# 09-modem3.net
KiCad netlist of a schematic drawn in Altium Designer
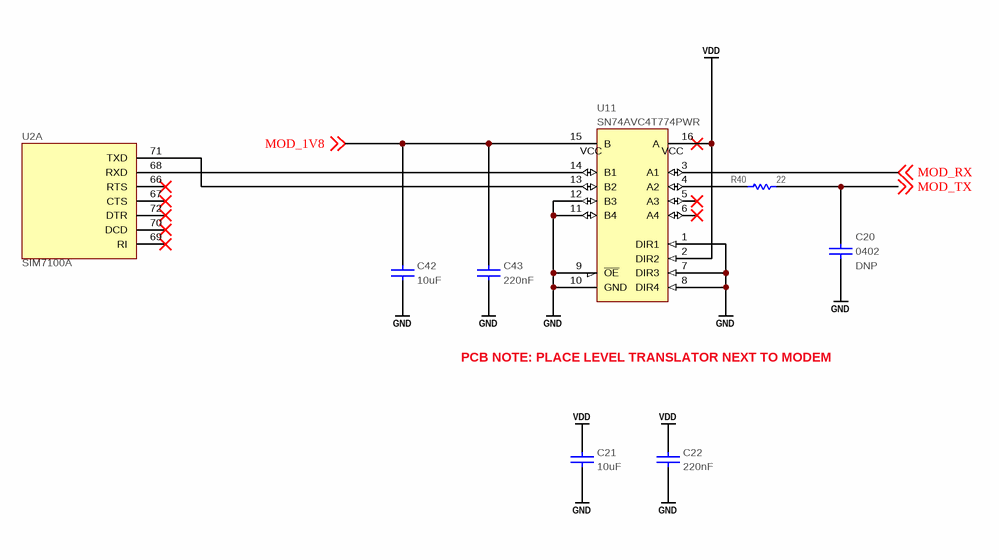
[diagram p0: 09-modem3.SchDoc]

(export (version "E")
  (design (tool "Eeschema 10.0.6"))
  (components
    (comp (ref "C20")
      (value "VJ0402A101KXA")
      (footprint "CAPC100X50X55L25N")
      (description "Ceramic Capacitor 100pF ±10% 50V C0G 0402")
      (fields
        (field (name "MANUFACTURER") "Vishay")
        (field (name "TOLERANCE") "±10%")
        (field (name "PACKAGE") "0402")
        (field (name "DO NOT PLACE") "DNP")
      )
      (libsource (lib "capacitors") (part "CAP"))
    )
    (comp (ref "C21")
      (value "10uF")
      (footprint "CAPC200X125X145L45N")
      (description "Ceramic Capacitor 10uF ±10% 16V X7R 0805")
      (fields (field (name "MANUFACTURER") "Samsung") (field (name "TOLERANCE") "±10%"))
      (libsource (lib "capacitors") (part "CAP"))
    )
    (comp (ref "C22")
      (value "220nF")
      (footprint "CAPC100X50X55L25N")
      (description "Ceramic Capacitor 220nF ±10% 25V X7R 0402")
      (fields (field (name "MANUFACTURER") "TDK") (field (name "TOLERANCE") "±10%"))
      (libsource (lib "capacitors") (part "CAP"))
    )
    (comp (ref "C42")
      (value "10uF")
      (footprint "CAPC200X125X145L45N")
      (description "Ceramic Capacitor 10uF ±10% 16V X7R 0805")
      (fields (field (name "MANUFACTURER") "Samsung") (field (name "TOLERANCE") "±10%"))
      (libsource (lib "capacitors") (part "CAP"))
    )
    (comp (ref "C43")
      (value "220nF")
      (footprint "CAPC100X50X55L25N")
      (description "Ceramic Capacitor 220nF ±10% 25V X7R 0402")
      (fields (field (name "MANUFACTURER") "TDK") (field (name "TOLERANCE") "±10%"))
      (libsource (lib "capacitors") (part "CAP"))
    )
    (comp (ref "R40")
      (value "22")
      (footprint "RESC2012X70N")
      (description "Thick Film Resistor 22 ±1% 0805")
      (fields (field (name "MANUFACTURER") "Panasonic") (field (name "TOLERANCE") "±1%"))
      (libsource (lib "Graviton") (part "RES 0402"))
    )
    (comp (ref "U2")
      (value "SIM7100A")
      (footprint "SIM7100A")
      (description "Cellular Module")
      (fields (field (name "MANUFACTURER") "SIMCOM"))
      (libsource (lib "simcom") (part "Component_1"))
    )
    (comp (ref "U11")
      (value "SN74AVC4T774PWR")
      (footprint "TSSOP16")
      (description "4-Bit Dual-Supply Bus Transceiver")
      (fields (field (name "MANUFACTURER") "Texas Instruments"))
      (libsource (lib "ti") (part "SN74AVC4T774PWR"))
    )
  )
  (nets
    (net (code "1") (name "GND") (class "Default")
      (node (ref "C20") (pin "2") (pinfunction "2_2") (pintype "passive"))
      (node (ref "C21") (pin "2") (pinfunction "2_2") (pintype "passive"))
      (node (ref "C22") (pin "2") (pinfunction "2_2") (pintype "passive"))
      (node (ref "C42") (pin "2") (pinfunction "2_2") (pintype "passive"))
      (node (ref "C43") (pin "2") (pinfunction "2_2") (pintype "passive"))
      (node (ref "U11") (pin "1") (pinfunction "DIR1_1") (pintype "input"))
      (node (ref "U11") (pin "10") (pinfunction "GND_10") (pintype "power_in"))
      (node (ref "U11") (pin "11") (pinfunction "B4_11") (pintype "bidirectional"))
      (node (ref "U11") (pin "12") (pinfunction "B3_12") (pintype "bidirectional"))
      (node (ref "U11") (pin "7") (pinfunction "DIR3_7") (pintype "input"))
      (node (ref "U11") (pin "8") (pinfunction "DIR4_8") (pintype "input"))
      (node (ref "U11") (pin "9") (pinfunction "OE_9") (pintype "passive"))
    )
    (net (code "2") (name "MOD_1V8") (class "Default")
      (node (ref "C42") (pin "1") (pinfunction "1_1") (pintype "passive"))
      (node (ref "C43") (pin "1") (pinfunction "1_1") (pintype "passive"))
      (node (ref "U11") (pin "15") (pinfunction "B_15") (pintype "power_in"))
    )
    (net (code "3") (name "MOD_RX") (class "Default")
      (node (ref "U11") (pin "3") (pinfunction "A1_3") (pintype "bidirectional"))
    )
    (net (code "4") (name "MOD_TX") (class "Default")
      (node (ref "C20") (pin "1") (pinfunction "1_1") (pintype "passive"))
      (node (ref "R40") (pin "1") (pinfunction "1_1") (pintype "passive"))
    )
    (net (code "5") (name "Net-(U11-A2)") (class "Default")
      (node (ref "R40") (pin "2") (pinfunction "2_2") (pintype "passive"))
      (node (ref "U11") (pin "4") (pinfunction "A2_4") (pintype "bidirectional"))
    )
    (net (code "6") (name "Net-(U11-B1)") (class "Default")
      (node (ref "U11") (pin "14") (pinfunction "B1_14") (pintype "bidirectional"))
      (node (ref "U2") (pin "68") (pinfunction "RXD_68") (pintype "passive"))
    )
    (net (code "7") (name "Net-(U11-B2)") (class "Default")
      (node (ref "U11") (pin "13") (pinfunction "B2_13") (pintype "bidirectional"))
      (node (ref "U2") (pin "71") (pinfunction "TXD_71") (pintype "passive"))
    )
    (net (code "8") (name "VDD") (class "Default")
      (node (ref "C21") (pin "1") (pinfunction "1_1") (pintype "passive"))
      (node (ref "C22") (pin "1") (pinfunction "1_1") (pintype "passive"))
      (node (ref "U11") (pin "16") (pinfunction "A_16") (pintype "power_in"))
      (node (ref "U11") (pin "2") (pinfunction "DIR2_2") (pintype "input"))
    )
    (net (code "9") (name "unconnected-(U2A-CTS-Pad67)") (class "Default")
      (node (ref "U2") (pin "67") (pinfunction "CTS_67") (pintype "passive+no_connect"))
    )
    (net (code "10") (name "unconnected-(U2A-DCD-Pad70)") (class "Default")
      (node (ref "U2") (pin "70") (pinfunction "DCD_70") (pintype "passive+no_connect"))
    )
    (net (code "11") (name "unconnected-(U2A-DTR-Pad72)") (class "Default")
      (node (ref "U2") (pin "72") (pinfunction "DTR_72") (pintype "passive+no_connect"))
    )
    (net (code "12") (name "unconnected-(U2A-RI-Pad69)") (class "Default")
      (node (ref "U2") (pin "69") (pinfunction "RI_69") (pintype "passive+no_connect"))
    )
    (net (code "13") (name "unconnected-(U2A-RTS-Pad66)") (class "Default")
      (node (ref "U2") (pin "66") (pinfunction "RTS_66") (pintype "passive+no_connect"))
    )
    (net (code "14") (name "unconnected-(U11-A3-Pad5)") (class "Default")
      (node (ref "U11") (pin "5") (pinfunction "A3_5") (pintype "bidirectional+no_connect"))
    )
    (net (code "15") (name "unconnected-(U11-A4-Pad6)") (class "Default")
      (node (ref "U11") (pin "6") (pinfunction "A4_6") (pintype "bidirectional+no_connect"))
    )
  )
)
